# P16_POWER1.net
KiCad netlist of a schematic drawn in Altium Designer
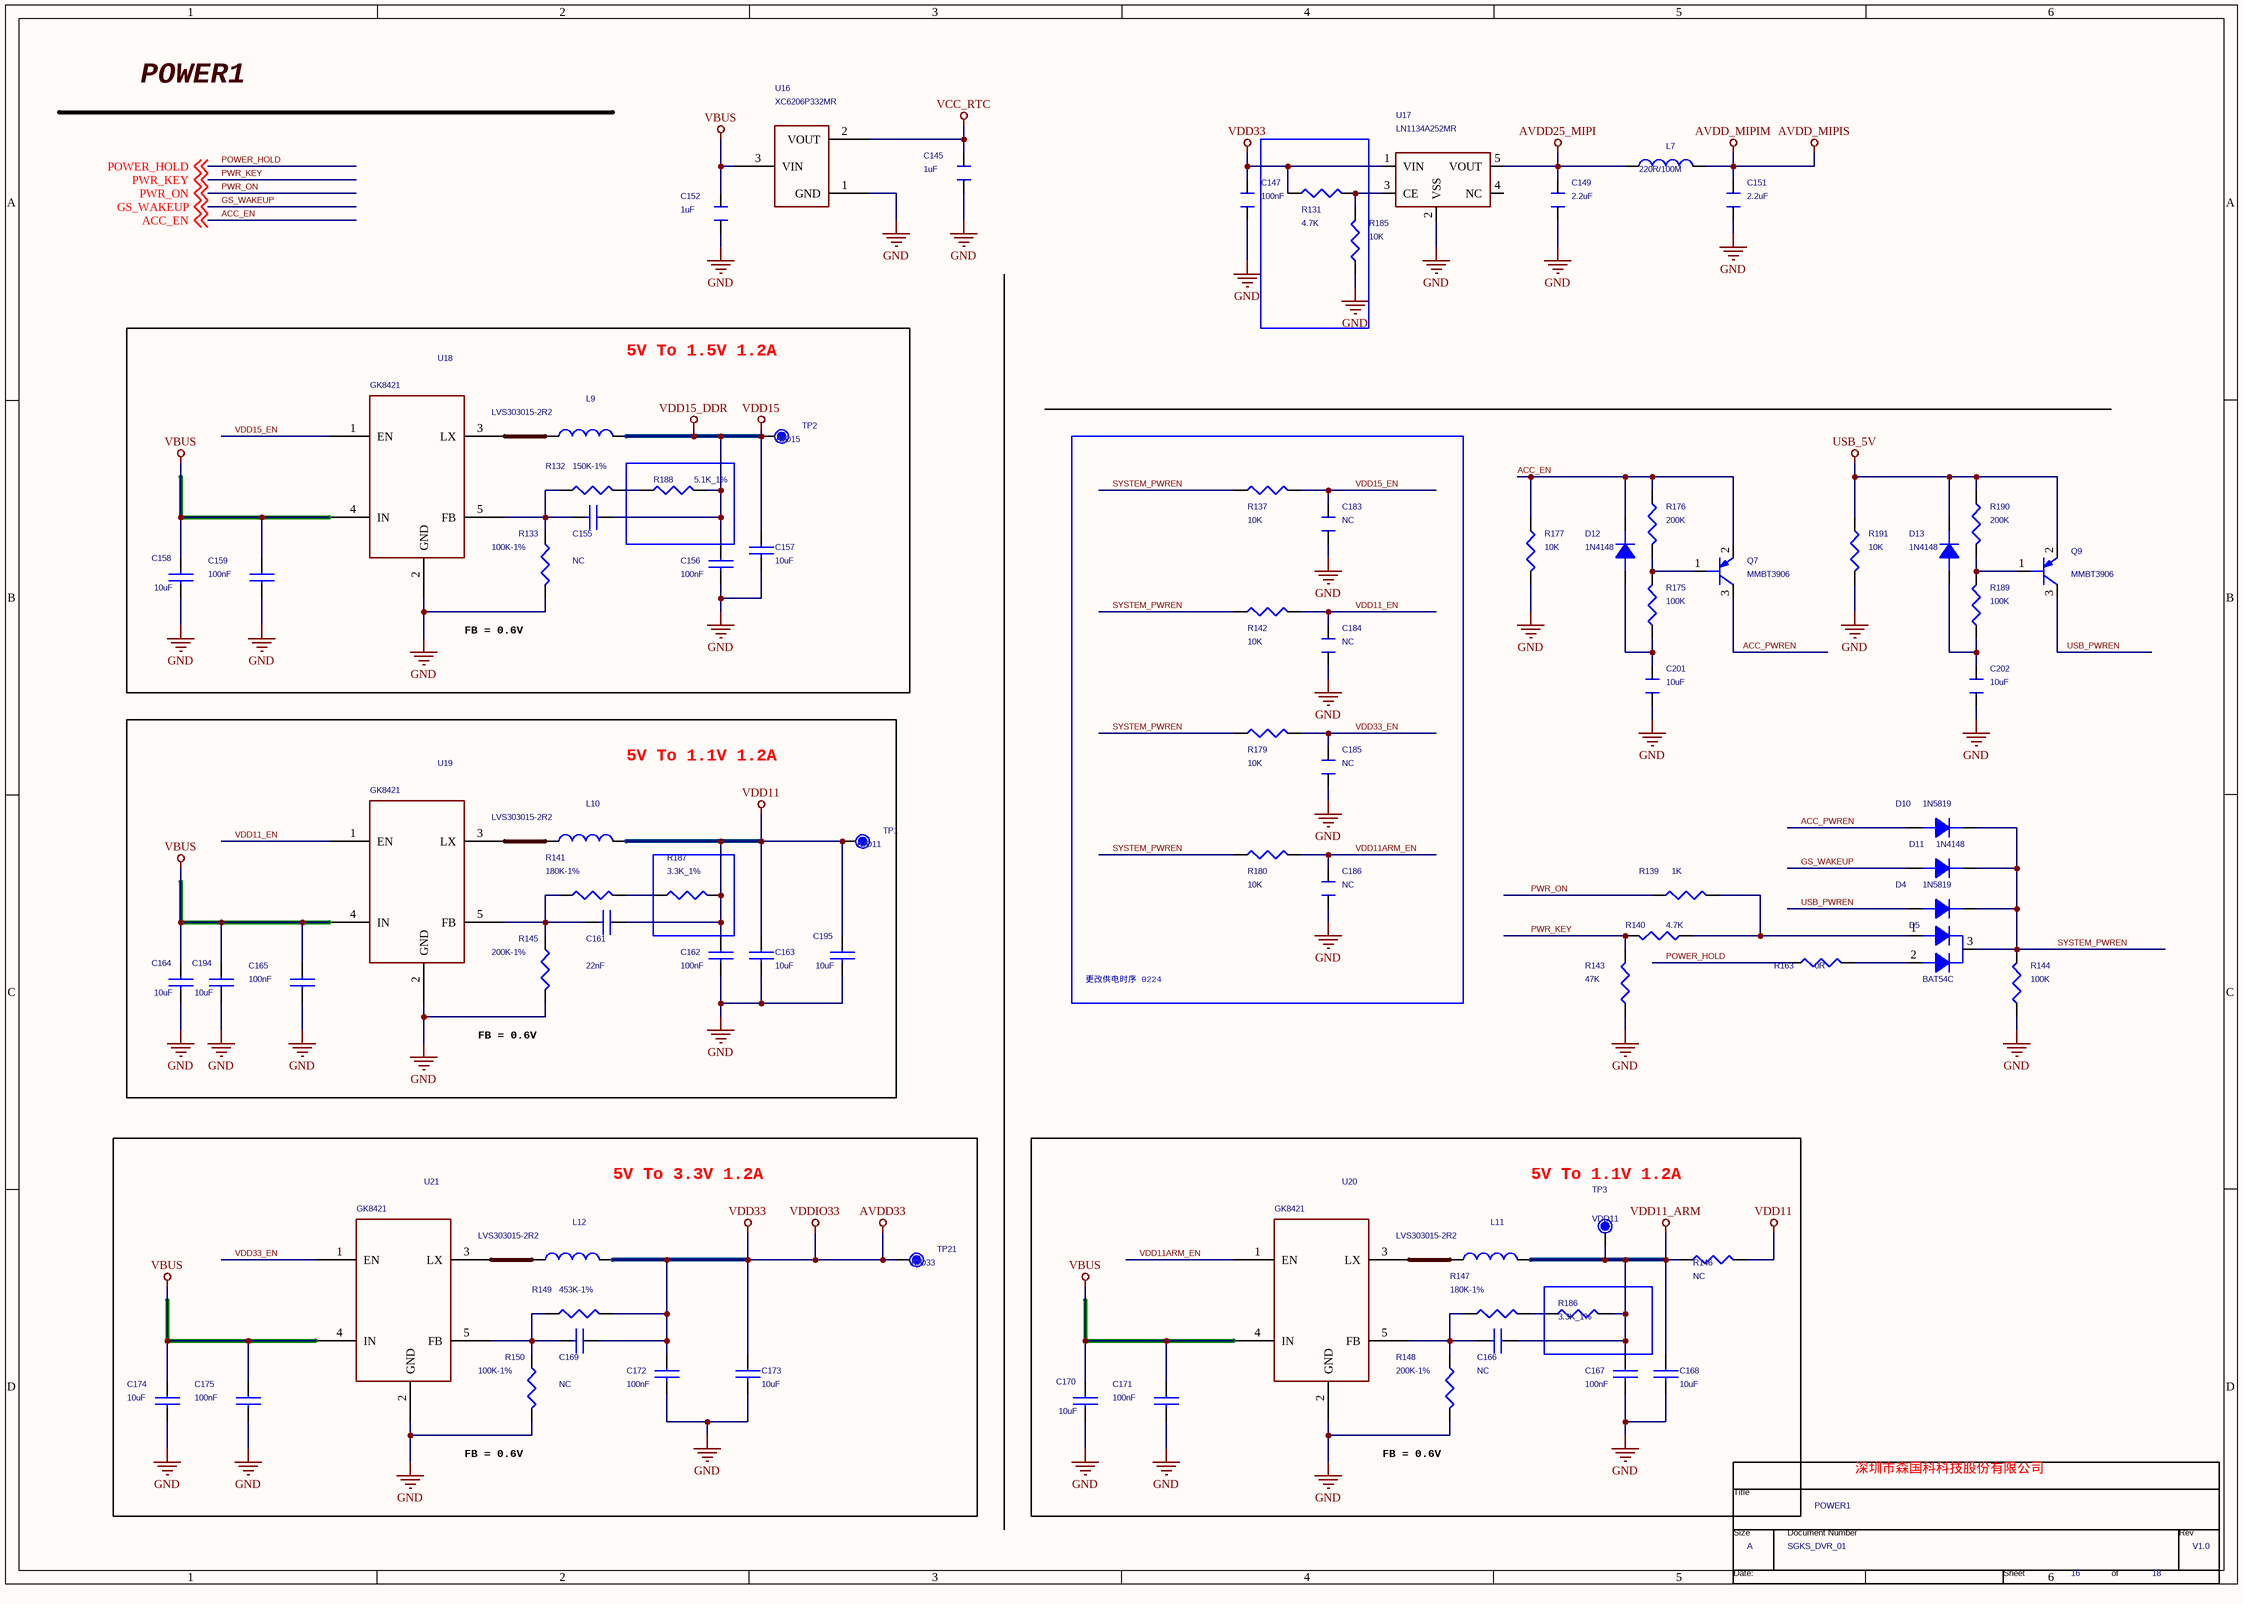
[diagram p0: P16 POWER1.SchDoc]

(export (version "E")
  (design (tool "Eeschema 10.0.6"))
  (components
    (comp (ref "C145") (value "1uF") (footprint "C0402") (libsource (lib "*") (part "CAPACITOR")))
    (comp (ref "C147") (value "100nF") (footprint "C0402") (libsource (lib "*") (part "CAPACITOR")))
    (comp (ref "C149") (value "2.2uF") (footprint "C0402") (libsource (lib "*") (part "CAPACITOR")))
    (comp (ref "C151") (value "2.2uF") (footprint "C0402") (libsource (lib "*") (part "CAPACITOR")))
    (comp (ref "C152") (value "1uF") (footprint "C0402") (libsource (lib "*") (part "CAPACITOR")))
    (comp (ref "C155") (value "NC") (footprint "C0402") (libsource (lib "*") (part "CAP")))
    (comp (ref "C156") (value "100nF") (footprint "C0402") (libsource (lib "*") (part "CAP")))
    (comp (ref "C157") (value "10uF") (footprint "C0603") (libsource (lib "*") (part "CAP")))
    (comp (ref "C158") (value "10uF") (footprint "C0603") (libsource (lib "*") (part "CAP")))
    (comp (ref "C159") (value "100nF") (footprint "C0402") (libsource (lib "*") (part "CAP")))
    (comp (ref "C161") (value "22nF") (footprint "C0402") (libsource (lib "*") (part "CAP")))
    (comp (ref "C162") (value "100nF") (footprint "C0402") (libsource (lib "*") (part "CAP")))
    (comp (ref "C163") (value "10uF") (footprint "C0603") (libsource (lib "*") (part "CAP")))
    (comp (ref "C164") (value "10uF") (footprint "C0603") (libsource (lib "*") (part "CAP")))
    (comp (ref "C165") (value "100nF") (footprint "C0402") (libsource (lib "*") (part "CAP")))
    (comp (ref "C166") (value "NC") (footprint "C0402") (libsource (lib "*") (part "CAP")))
    (comp (ref "C167") (value "100nF") (footprint "C0402") (libsource (lib "*") (part "CAP")))
    (comp (ref "C168") (value "10uF") (footprint "C0603") (libsource (lib "*") (part "CAP")))
    (comp (ref "C169") (value "NC") (footprint "C0402") (libsource (lib "*") (part "CAP")))
    (comp (ref "C170") (value "10uF") (footprint "C0603") (libsource (lib "*") (part "CAP")))
    (comp (ref "C171") (value "100nF") (footprint "C0402") (libsource (lib "*") (part "CAP")))
    (comp (ref "C172") (value "100nF") (footprint "C0402") (libsource (lib "*") (part "CAP")))
    (comp (ref "C173") (value "10uF") (footprint "C0603") (libsource (lib "*") (part "CAP")))
    (comp (ref "C174") (value "10uF") (footprint "C0603") (libsource (lib "*") (part "CAP")))
    (comp (ref "C175") (value "100nF") (footprint "C0402") (libsource (lib "*") (part "CAP")))
    (comp (ref "C183") (value "NC") (footprint "C0402") (libsource (lib "*") (part "CAPACITOR")))
    (comp (ref "C184") (value "NC") (footprint "C0402") (libsource (lib "*") (part "CAPACITOR")))
    (comp (ref "C185") (value "NC") (footprint "C0402") (libsource (lib "*") (part "CAPACITOR")))
    (comp (ref "C186") (value "NC") (footprint "C0402") (libsource (lib "*") (part "CAPACITOR")))
    (comp (ref "C194") (value "10uF") (footprint "C0603") (libsource (lib "*") (part "CAP")))
    (comp (ref "C195") (value "10uF") (footprint "C0603") (libsource (lib "*") (part "CAP")))
    (comp (ref "C201") (value "10uF") (footprint "C0603") (libsource (lib "*") (part "CAPACITOR")))
    (comp (ref "C202") (value "10uF") (footprint "C0603") (libsource (lib "*") (part "CAPACITOR")))
    (comp (ref "D4") (value "1N5819") (footprint "SOD-123") (libsource (lib "*") (part "DIODE")))
    (comp (ref "D5")
      (value "BAT54C")
      (footprint "SOT-23")
      (description "二极管")
      (libsource (lib "*") (part "DIODE_1"))
    )
    (comp (ref "D10") (value "1N5819") (footprint "SOD-123") (libsource (lib "*") (part "DIODE")))
    (comp (ref "D11") (value "1N4148") (footprint "SOD-123") (libsource (lib "*") (part "DIODE")))
    (comp (ref "D12") (value "1N4148") (footprint "SOD-123") (libsource (lib "*") (part "DIODE")))
    (comp (ref "D13") (value "1N4148") (footprint "SOD-123") (libsource (lib "*") (part "DIODE")))
    (comp (ref "L7") (value "220R/100M") (footprint "L0402") (libsource (lib "*") (part "INDUCTOR_2")))
    (comp (ref "L9") (value "LVS303015-2R2") (footprint "PL4X4") (libsource (lib "*") (part "INDUCTOR_Dup1")))
    (comp (ref "L10")
      (value "LVS303015-2R2")
      (footprint "PL4X4")
      (libsource (lib "*") (part "INDUCTOR_Dup1"))
    )
    (comp (ref "L11")
      (value "LVS303015-2R2")
      (footprint "PL4X4")
      (libsource (lib "*") (part "INDUCTOR_Dup1"))
    )
    (comp (ref "L12")
      (value "LVS303015-2R2")
      (footprint "PL4X4")
      (libsource (lib "*") (part "INDUCTOR_Dup1"))
    )
    (comp (ref "Q7") (value "MMBT3906") (footprint "SOT-23") (libsource (lib "*") (part "PNP CEB")))
    (comp (ref "Q9") (value "MMBT3906") (footprint "SOT-23") (libsource (lib "*") (part "PNP CEB")))
    (comp (ref "R131") (value "4.7K") (footprint "R0603/SMD") (libsource (lib "*") (part "RES/SMD_1")))
    (comp (ref "R132") (value "150K-1%") (footprint "R0402") (libsource (lib "*") (part "RESISTOR_Dup2")))
    (comp (ref "R133") (value "100K-1%") (footprint "R0402") (libsource (lib "*") (part "RESISTOR_Dup2")))
    (comp (ref "R137") (value "10K") (footprint "R0402") (libsource (lib "*") (part "R_Dup1")))
    (comp (ref "R139") (value "1K") (footprint "R0402") (libsource (lib "*") (part "R")))
    (comp (ref "R140") (value "4.7K") (footprint "R0402") (libsource (lib "*") (part "R_Dup1")))
    (comp (ref "R141") (value "180K-1%") (footprint "R0402") (libsource (lib "*") (part "RESISTOR_Dup2")))
    (comp (ref "R142") (value "10K") (footprint "R0402") (libsource (lib "*") (part "R_Dup1")))
    (comp (ref "R143") (value "47K") (footprint "R0402") (libsource (lib "*") (part "R_Dup1")))
    (comp (ref "R144") (value "100K") (footprint "R0402") (libsource (lib "*") (part "R_Dup1")))
    (comp (ref "R145") (value "200K-1%") (footprint "R0402") (libsource (lib "*") (part "RESISTOR_Dup2")))
    (comp (ref "R146") (value "NC") (footprint "R0603") (libsource (lib "*") (part "RESISTOR_Dup2")))
    (comp (ref "R147") (value "180K-1%") (footprint "R0402") (libsource (lib "*") (part "RESISTOR_Dup2")))
    (comp (ref "R148") (value "200K-1%") (footprint "R0402") (libsource (lib "*") (part "RESISTOR_Dup2")))
    (comp (ref "R149") (value "453K-1%") (footprint "R0402") (libsource (lib "*") (part "RESISTOR_Dup2")))
    (comp (ref "R150") (value "100K-1%") (footprint "R0402") (libsource (lib "*") (part "RESISTOR_Dup2")))
    (comp (ref "R163") (value "0R") (footprint "R0402") (libsource (lib "*") (part "R")))
    (comp (ref "R175") (value "100K") (footprint "R0402") (libsource (lib "*") (part "R")))
    (comp (ref "R176") (value "200K") (footprint "R0402") (libsource (lib "*") (part "R")))
    (comp (ref "R177") (value "10K") (footprint "R0402") (libsource (lib "*") (part "R_Dup1")))
    (comp (ref "R179") (value "10K") (footprint "R0402") (libsource (lib "*") (part "R_Dup1")))
    (comp (ref "R180") (value "10K") (footprint "R0402") (libsource (lib "*") (part "R_Dup1")))
    (comp (ref "R185") (value "10K") (footprint "R0603/SMD") (libsource (lib "*") (part "RES/SMD_1")))
    (comp (ref "R186") (value "3.3K_1%") (footprint "R0402") (libsource (lib "*") (part "RESISTOR_Dup2")))
    (comp (ref "R187") (value "3.3K_1%") (footprint "R0402") (libsource (lib "*") (part "RESISTOR_Dup2")))
    (comp (ref "R188") (value "5.1K_1%") (footprint "R0402") (libsource (lib "*") (part "RESISTOR_Dup2")))
    (comp (ref "R189") (value "100K") (footprint "R0402") (libsource (lib "*") (part "R")))
    (comp (ref "R190") (value "200K") (footprint "R0402") (libsource (lib "*") (part "R")))
    (comp (ref "R191") (value "10K") (footprint "R0402") (libsource (lib "*") (part "R_Dup1")))
    (comp (ref "TP1") (value "VDD11") (footprint "TP/SMD/D1.0") (libsource (lib "*") (part "TP_0")))
    (comp (ref "TP2") (value "VDD15") (footprint "TP/SMD/D1.0") (libsource (lib "*") (part "TP_0")))
    (comp (ref "TP3") (value "VDD11") (footprint "TP/SMD/D1.0") (libsource (lib "*") (part "TP_0")))
    (comp (ref "TP21") (value "VDD33") (footprint "TP/SMD/D1.0") (libsource (lib "*") (part "TP_0")))
    (comp (ref "U16") (value "XC6206P332MR") (footprint "SOT-23") (libsource (lib "*") (part "RT9166")))
    (comp (ref "U17") (value "LN1134A252MR") (footprint "SOT23-6") (libsource (lib "*") (part "RT9266PE_0")))
    (comp (ref "U18") (value "GK8421") (footprint "SOT23-5") (libsource (lib "*") (part "MP2161_2")))
    (comp (ref "U19") (value "GK8421") (footprint "SOT23-5") (libsource (lib "*") (part "MP2161_2")))
    (comp (ref "U20") (value "GK8421") (footprint "SOT23-5") (libsource (lib "*") (part "MP2161_2")))
    (comp (ref "U21") (value "GK8421") (footprint "SOT23-5") (libsource (lib "*") (part "MP2161_2")))
  )
  (nets
    (net (code "1") (name "/ACC_PWREN") (class "Default")
      (node (ref "D10") (pin "1") (pinfunction "A_1") (pintype "passive"))
      (node (ref "Q7") (pin "3") (pinfunction "C_3") (pintype "passive"))
    )
    (net (code "2") (name "/SYSTEM_PWREN") (class "Default")
      (node (ref "D10") (pin "2") (pinfunction "K_2") (pintype "passive"))
      (node (ref "D11") (pin "2") (pinfunction "K_2") (pintype "passive"))
      (node (ref "D4") (pin "2") (pinfunction "K_2") (pintype "passive"))
      (node (ref "D5") (pin "3") (pinfunction "K_3") (pintype "passive"))
      (node (ref "R137") (pin "1") (pinfunction "1_1") (pintype "passive"))
      (node (ref "R142") (pin "1") (pinfunction "1_1") (pintype "passive"))
      (node (ref "R144") (pin "1") (pinfunction "1_1") (pintype "passive"))
      (node (ref "R179") (pin "1") (pinfunction "1_1") (pintype "passive"))
      (node (ref "R180") (pin "1") (pinfunction "1_1") (pintype "passive"))
    )
    (net (code "3") (name "/USB_PWREN") (class "Default")
      (node (ref "D4") (pin "1") (pinfunction "A_1") (pintype "passive"))
      (node (ref "Q9") (pin "3") (pinfunction "C_3") (pintype "passive"))
    )
    (net (code "4") (name "/VDD11ARM_EN") (class "Default")
      (node (ref "C186") (pin "2") (pinfunction "2_2") (pintype "passive"))
      (node (ref "R180") (pin "2") (pinfunction "2_2") (pintype "passive"))
      (node (ref "U20") (pin "1") (pinfunction "EN_1") (pintype "passive"))
    )
    (net (code "5") (name "/VDD11_EN") (class "Default")
      (node (ref "C184") (pin "2") (pinfunction "2_2") (pintype "passive"))
      (node (ref "R142") (pin "2") (pinfunction "2_2") (pintype "passive"))
      (node (ref "U19") (pin "1") (pinfunction "EN_1") (pintype "passive"))
    )
    (net (code "6") (name "/VDD15_EN") (class "Default")
      (node (ref "C183") (pin "2") (pinfunction "2_2") (pintype "passive"))
      (node (ref "R137") (pin "2") (pinfunction "2_2") (pintype "passive"))
      (node (ref "U18") (pin "1") (pinfunction "EN_1") (pintype "passive"))
    )
    (net (code "7") (name "/VDD33_EN") (class "Default")
      (node (ref "C185") (pin "2") (pinfunction "2_2") (pintype "passive"))
      (node (ref "R179") (pin "2") (pinfunction "2_2") (pintype "passive"))
      (node (ref "U21") (pin "1") (pinfunction "EN_1") (pintype "passive"))
    )
    (net (code "8") (name "ACC_EN") (class "Default")
      (node (ref "D12") (pin "2") (pinfunction "K_2") (pintype "passive"))
      (node (ref "Q7") (pin "2") (pinfunction "E_2") (pintype "passive"))
      (node (ref "R176") (pin "1") (pinfunction "1_1") (pintype "passive"))
      (node (ref "R177") (pin "1") (pinfunction "1_1") (pintype "passive"))
    )
    (net (code "9") (name "AVDD25_MIPI") (class "Default")
      (node (ref "C149") (pin "2") (pinfunction "2_2") (pintype "passive"))
      (node (ref "L7") (pin "2") (pinfunction "2_2") (pintype "passive"))
      (node (ref "U17") (pin "5") (pinfunction "VOUT_5") (pintype "passive"))
    )
    (net (code "10") (name "AVDD33") (class "Default")
      (node (ref "C147") (pin "2") (pinfunction "2_2") (pintype "passive"))
      (node (ref "C169") (pin "1") (pinfunction "1_1") (pintype "passive"))
      (node (ref "C172") (pin "1") (pinfunction "1_1") (pintype "passive"))
      (node (ref "C173") (pin "1") (pinfunction "1_1") (pintype "passive"))
      (node (ref "L12") (pin "2") (pinfunction "2_2") (pintype "passive"))
      (node (ref "R131") (pin "1") (pinfunction "1_1") (pintype "passive"))
      (node (ref "R149") (pin "1") (pinfunction "1_1") (pintype "passive"))
      (node (ref "TP21") (pin "1") (pinfunction "1_1") (pintype "passive"))
      (node (ref "U17") (pin "1") (pinfunction "VIN_1") (pintype "passive"))
    )
    (net (code "11") (name "AVDD_MIPIM") (class "Default")
      (node (ref "C151") (pin "2") (pinfunction "2_2") (pintype "passive"))
      (node (ref "L7") (pin "1") (pinfunction "1_1") (pintype "passive"))
    )
    (net (code "12") (name "GND") (class "Default")
      (node (ref "C145") (pin "1") (pinfunction "1_1") (pintype "passive"))
      (node (ref "C147") (pin "1") (pinfunction "1_1") (pintype "passive"))
      (node (ref "C149") (pin "1") (pinfunction "1_1") (pintype "passive"))
      (node (ref "C151") (pin "1") (pinfunction "1_1") (pintype "passive"))
      (node (ref "C152") (pin "1") (pinfunction "1_1") (pintype "passive"))
      (node (ref "C156") (pin "2") (pinfunction "2_2") (pintype "passive"))
      (node (ref "C157") (pin "2") (pinfunction "2_2") (pintype "passive"))
      (node (ref "C158") (pin "2") (pinfunction "2_2") (pintype "passive"))
      (node (ref "C159") (pin "2") (pinfunction "2_2") (pintype "passive"))
      (node (ref "C162") (pin "2") (pinfunction "2_2") (pintype "passive"))
      (node (ref "C163") (pin "2") (pinfunction "2_2") (pintype "passive"))
      (node (ref "C164") (pin "2") (pinfunction "2_2") (pintype "passive"))
      (node (ref "C165") (pin "2") (pinfunction "2_2") (pintype "passive"))
      (node (ref "C167") (pin "2") (pinfunction "2_2") (pintype "passive"))
      (node (ref "C168") (pin "2") (pinfunction "2_2") (pintype "passive"))
      (node (ref "C170") (pin "2") (pinfunction "2_2") (pintype "passive"))
      (node (ref "C171") (pin "2") (pinfunction "2_2") (pintype "passive"))
      (node (ref "C172") (pin "2") (pinfunction "2_2") (pintype "passive"))
      (node (ref "C173") (pin "2") (pinfunction "2_2") (pintype "passive"))
      (node (ref "C174") (pin "2") (pinfunction "2_2") (pintype "passive"))
      (node (ref "C175") (pin "2") (pinfunction "2_2") (pintype "passive"))
      (node (ref "C183") (pin "1") (pinfunction "1_1") (pintype "passive"))
      (node (ref "C184") (pin "1") (pinfunction "1_1") (pintype "passive"))
      (node (ref "C185") (pin "1") (pinfunction "1_1") (pintype "passive"))
      (node (ref "C186") (pin "1") (pinfunction "1_1") (pintype "passive"))
      (node (ref "C194") (pin "2") (pinfunction "2_2") (pintype "passive"))
      (node (ref "C195") (pin "2") (pinfunction "2_2") (pintype "passive"))
      (node (ref "C201") (pin "1") (pinfunction "1_1") (pintype "passive"))
      (node (ref "C202") (pin "1") (pinfunction "1_1") (pintype "passive"))
      (node (ref "R133") (pin "2") (pinfunction "2_2") (pintype "passive"))
      (node (ref "R143") (pin "2") (pinfunction "2_2") (pintype "passive"))
      (node (ref "R144") (pin "2") (pinfunction "2_2") (pintype "passive"))
      (node (ref "R145") (pin "2") (pinfunction "2_2") (pintype "passive"))
      (node (ref "R148") (pin "2") (pinfunction "2_2") (pintype "passive"))
      (node (ref "R150") (pin "2") (pinfunction "2_2") (pintype "passive"))
      (node (ref "R177") (pin "2") (pinfunction "2_2") (pintype "passive"))
      (node (ref "R185") (pin "1") (pinfunction "1_1") (pintype "passive"))
      (node (ref "R191") (pin "2") (pinfunction "2_2") (pintype "passive"))
      (node (ref "U16") (pin "1") (pinfunction "GND_1") (pintype "power_in"))
      (node (ref "U17") (pin "2") (pinfunction "VSS_2") (pintype "passive"))
      (node (ref "U18") (pin "2") (pinfunction "GND_2") (pintype "passive"))
      (node (ref "U19") (pin "2") (pinfunction "GND_2") (pintype "passive"))
      (node (ref "U20") (pin "2") (pinfunction "GND_2") (pintype "passive"))
      (node (ref "U21") (pin "2") (pinfunction "GND_2") (pintype "passive"))
    )
    (net (code "13") (name "GS_WAKEUP") (class "Default")
      (node (ref "D11") (pin "1") (pinfunction "A_1") (pintype "passive"))
    )
    (net (code "14") (name "Net-(D5-A1)") (class "Default")
      (node (ref "D5") (pin "1") (pinfunction "A1_1") (pintype "passive"))
      (node (ref "R139") (pin "1") (pinfunction "1_1") (pintype "passive"))
      (node (ref "R140") (pin "2") (pinfunction "2_2") (pintype "passive"))
    )
    (net (code "15") (name "Net-(D5-A2)") (class "Default")
      (node (ref "D5") (pin "2") (pinfunction "A2_2") (pintype "passive"))
      (node (ref "R163") (pin "1") (pinfunction "1_1") (pintype "passive"))
    )
    (net (code "16") (name "Net-(D12-A)") (class "Default")
      (node (ref "C201") (pin "2") (pinfunction "2_2") (pintype "passive"))
      (node (ref "D12") (pin "1") (pinfunction "A_1") (pintype "passive"))
      (node (ref "R175") (pin "1") (pinfunction "1_1") (pintype "passive"))
    )
    (net (code "17") (name "Net-(D13-A)") (class "Default")
      (node (ref "C202") (pin "2") (pinfunction "2_2") (pintype "passive"))
      (node (ref "D13") (pin "1") (pinfunction "A_1") (pintype "passive"))
      (node (ref "R189") (pin "1") (pinfunction "1_1") (pintype "passive"))
    )
    (net (code "18") (name "Net-(Q7-B)") (class "Default")
      (node (ref "Q7") (pin "1") (pinfunction "B_1") (pintype "passive"))
      (node (ref "R175") (pin "2") (pinfunction "2_2") (pintype "passive"))
      (node (ref "R176") (pin "2") (pinfunction "2_2") (pintype "passive"))
    )
    (net (code "19") (name "Net-(Q9-B)") (class "Default")
      (node (ref "Q9") (pin "1") (pinfunction "B_1") (pintype "passive"))
      (node (ref "R189") (pin "2") (pinfunction "2_2") (pintype "passive"))
      (node (ref "R190") (pin "2") (pinfunction "2_2") (pintype "passive"))
    )
    (net (code "20") (name "Net-(R132-Pad1)") (class "Default")
      (node (ref "R132") (pin "1") (pinfunction "1_1") (pintype "passive"))
      (node (ref "R188") (pin "2") (pinfunction "2_2") (pintype "passive"))
    )
    (net (code "21") (name "Net-(R141-Pad1)") (class "Default")
      (node (ref "R141") (pin "1") (pinfunction "1_1") (pintype "passive"))
      (node (ref "R187") (pin "2") (pinfunction "2_2") (pintype "passive"))
    )
    (net (code "22") (name "Net-(R147-Pad1)") (class "Default")
      (node (ref "R147") (pin "1") (pinfunction "1_1") (pintype "passive"))
      (node (ref "R186") (pin "2") (pinfunction "2_2") (pintype "passive"))
    )
    (net (code "23") (name "Net-(U17-CE)") (class "Default")
      (node (ref "R131") (pin "2") (pinfunction "2_2") (pintype "passive"))
      (node (ref "R185") (pin "2") (pinfunction "2_2") (pintype "passive"))
      (node (ref "U17") (pin "3") (pinfunction "CE_3") (pintype "passive"))
    )
    (net (code "24") (name "Net-(U18-FB)") (class "Default")
      (node (ref "C155") (pin "2") (pinfunction "2_2") (pintype "passive"))
      (node (ref "R132") (pin "2") (pinfunction "2_2") (pintype "passive"))
      (node (ref "R133") (pin "1") (pinfunction "1_1") (pintype "passive"))
      (node (ref "U18") (pin "5") (pinfunction "FB_5") (pintype "passive"))
    )
    (net (code "25") (name "Net-(U18-LX)") (class "Default")
      (node (ref "L9") (pin "1") (pinfunction "1_1") (pintype "passive"))
      (node (ref "U18") (pin "3") (pinfunction "LX_3") (pintype "passive"))
    )
    (net (code "26") (name "Net-(U19-FB)") (class "Default")
      (node (ref "C161") (pin "2") (pinfunction "2_2") (pintype "passive"))
      (node (ref "R141") (pin "2") (pinfunction "2_2") (pintype "passive"))
      (node (ref "R145") (pin "1") (pinfunction "1_1") (pintype "passive"))
      (node (ref "U19") (pin "5") (pinfunction "FB_5") (pintype "passive"))
    )
    (net (code "27") (name "Net-(U19-LX)") (class "Default")
      (node (ref "L10") (pin "1") (pinfunction "1_1") (pintype "passive"))
      (node (ref "U19") (pin "3") (pinfunction "LX_3") (pintype "passive"))
    )
    (net (code "28") (name "Net-(U20-FB)") (class "Default")
      (node (ref "C166") (pin "2") (pinfunction "2_2") (pintype "passive"))
      (node (ref "R147") (pin "2") (pinfunction "2_2") (pintype "passive"))
      (node (ref "R148") (pin "1") (pinfunction "1_1") (pintype "passive"))
      (node (ref "U20") (pin "5") (pinfunction "FB_5") (pintype "passive"))
    )
    (net (code "29") (name "Net-(U20-LX)") (class "Default")
      (node (ref "L11") (pin "1") (pinfunction "1_1") (pintype "passive"))
      (node (ref "U20") (pin "3") (pinfunction "LX_3") (pintype "passive"))
    )
    (net (code "30") (name "Net-(U21-FB)") (class "Default")
      (node (ref "C169") (pin "2") (pinfunction "2_2") (pintype "passive"))
      (node (ref "R149") (pin "2") (pinfunction "2_2") (pintype "passive"))
      (node (ref "R150") (pin "1") (pinfunction "1_1") (pintype "passive"))
      (node (ref "U21") (pin "5") (pinfunction "FB_5") (pintype "passive"))
    )
    (net (code "31") (name "Net-(U21-LX)") (class "Default")
      (node (ref "L12") (pin "1") (pinfunction "1_1") (pintype "passive"))
      (node (ref "U21") (pin "3") (pinfunction "LX_3") (pintype "passive"))
    )
    (net (code "32") (name "POWER_HOLD") (class "Default")
      (node (ref "R163") (pin "2") (pinfunction "2_2") (pintype "passive"))
    )
    (net (code "33") (name "PWR_KEY") (class "Default")
      (node (ref "R140") (pin "1") (pinfunction "1_1") (pintype "passive"))
      (node (ref "R143") (pin "1") (pinfunction "1_1") (pintype "passive"))
    )
    (net (code "34") (name "PWR_ON") (class "Default")
      (node (ref "R139") (pin "2") (pinfunction "2_2") (pintype "passive"))
    )
    (net (code "35") (name "USB_5V") (class "Default")
      (node (ref "D13") (pin "2") (pinfunction "K_2") (pintype "passive"))
      (node (ref "Q9") (pin "2") (pinfunction "E_2") (pintype "passive"))
      (node (ref "R190") (pin "1") (pinfunction "1_1") (pintype "passive"))
      (node (ref "R191") (pin "1") (pinfunction "1_1") (pintype "passive"))
    )
    (net (code "36") (name "VBUS") (class "Default")
      (node (ref "C152") (pin "2") (pinfunction "2_2") (pintype "passive"))
      (node (ref "C158") (pin "1") (pinfunction "1_1") (pintype "passive"))
      (node (ref "C159") (pin "1") (pinfunction "1_1") (pintype "passive"))
      (node (ref "C164") (pin "1") (pinfunction "1_1") (pintype "passive"))
      (node (ref "C165") (pin "1") (pinfunction "1_1") (pintype "passive"))
      (node (ref "C170") (pin "1") (pinfunction "1_1") (pintype "passive"))
      (node (ref "C171") (pin "1") (pinfunction "1_1") (pintype "passive"))
      (node (ref "C174") (pin "1") (pinfunction "1_1") (pintype "passive"))
      (node (ref "C175") (pin "1") (pinfunction "1_1") (pintype "passive"))
      (node (ref "C194") (pin "1") (pinfunction "1_1") (pintype "passive"))
      (node (ref "U16") (pin "3") (pinfunction "VIN_3") (pintype "power_in"))
      (node (ref "U18") (pin "4") (pinfunction "IN_4") (pintype "passive"))
      (node (ref "U19") (pin "4") (pinfunction "IN_4") (pintype "passive"))
      (node (ref "U20") (pin "4") (pinfunction "IN_4") (pintype "passive"))
      (node (ref "U21") (pin "4") (pinfunction "IN_4") (pintype "passive"))
    )
    (net (code "37") (name "VCC_RTC") (class "Default")
      (node (ref "C145") (pin "2") (pinfunction "2_2") (pintype "passive"))
      (node (ref "U16") (pin "2") (pinfunction "VOUT_2") (pintype "power_in"))
    )
    (net (code "38") (name "VDD11") (class "Default")
      (node (ref "C161") (pin "1") (pinfunction "1_1") (pintype "passive"))
      (node (ref "C162") (pin "1") (pinfunction "1_1") (pintype "passive"))
      (node (ref "C163") (pin "1") (pinfunction "1_1") (pintype "passive"))
      (node (ref "C195") (pin "1") (pinfunction "1_1") (pintype "passive"))
      (node (ref "L10") (pin "2") (pinfunction "2_2") (pintype "passive"))
      (node (ref "R146") (pin "2") (pinfunction "2_2") (pintype "passive"))
      (node (ref "R187") (pin "1") (pinfunction "1_1") (pintype "passive"))
      (node (ref "TP1") (pin "1") (pinfunction "1_1") (pintype "passive"))
    )
    (net (code "39") (name "VDD11_ARM") (class "Default")
      (node (ref "C166") (pin "1") (pinfunction "1_1") (pintype "passive"))
      (node (ref "C167") (pin "1") (pinfunction "1_1") (pintype "passive"))
      (node (ref "C168") (pin "1") (pinfunction "1_1") (pintype "passive"))
      (node (ref "L11") (pin "2") (pinfunction "2_2") (pintype "passive"))
      (node (ref "R146") (pin "1") (pinfunction "1_1") (pintype "passive"))
      (node (ref "R186") (pin "1") (pinfunction "1_1") (pintype "passive"))
      (node (ref "TP3") (pin "1") (pinfunction "1_1") (pintype "passive"))
    )
    (net (code "40") (name "VDD15") (class "Default")
      (node (ref "C155") (pin "1") (pinfunction "1_1") (pintype "passive"))
      (node (ref "C156") (pin "1") (pinfunction "1_1") (pintype "passive"))
      (node (ref "C157") (pin "1") (pinfunction "1_1") (pintype "passive"))
      (node (ref "L9") (pin "2") (pinfunction "2_2") (pintype "passive"))
      (node (ref "R188") (pin "1") (pinfunction "1_1") (pintype "passive"))
      (node (ref "TP2") (pin "1") (pinfunction "1_1") (pintype "passive"))
    )
    (net (code "41") (name "unconnected-(U17-NC-Pad4)") (class "Default")
      (node (ref "U17") (pin "4") (pinfunction "NC_4") (pintype "passive"))
    )
  )
)
